# analog.net
KiCad netlist of a schematic drawn in Altium Designer
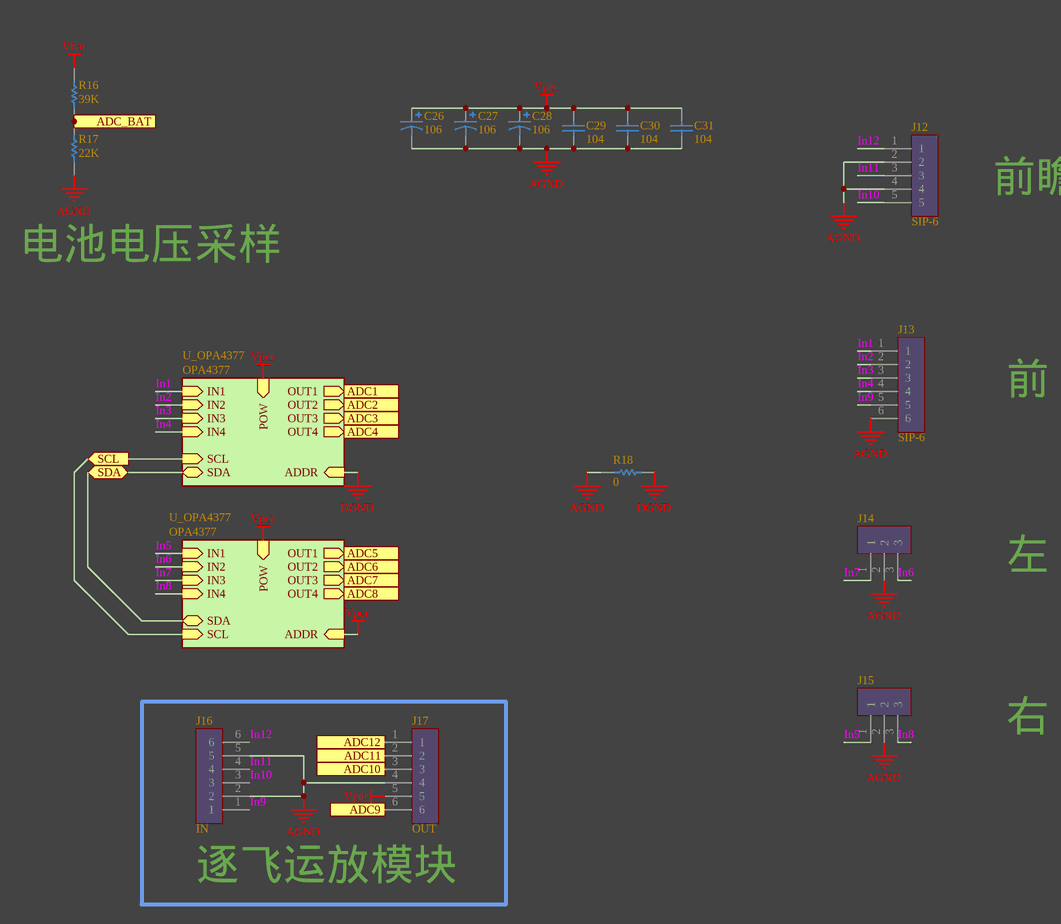
[diagram p0: analog.SchDoc]

(export (version "E")
  (design (tool "Eeschema 10.0.6"))
  (components
    (comp (ref "C26")
      (value "106")
      (footprint "3216-ce")
      (description "Polarized Capacitor (Axial)")
      (fields (field (name "PUBLISHER") "Altium Limited"))
      (libsource (lib "iMag") (part "电解电容"))
    )
    (comp (ref "C27")
      (value "106")
      (footprint "3216-ce")
      (description "Polarized Capacitor (Axial)")
      (fields (field (name "PUBLISHER") "Altium Limited"))
      (libsource (lib "iMag") (part "电解电容"))
    )
    (comp (ref "C28")
      (value "106")
      (footprint "3216-ce")
      (description "Polarized Capacitor (Axial)")
      (fields (field (name "PUBLISHER") "Altium Limited"))
      (libsource (lib "iMag") (part "电解电容"))
    )
    (comp (ref "C29")
      (value "104")
      (footprint "C0402")
      (description "Capacitor")
      (fields (field (name "PUBLISHER") "Altium Limited"))
      (libsource (lib "iMag") (part "电容"))
    )
    (comp (ref "C30")
      (value "104")
      (footprint "C0402")
      (description "Capacitor")
      (fields (field (name "PUBLISHER") "Altium Limited"))
      (libsource (lib "iMag") (part "电容"))
    )
    (comp (ref "C31")
      (value "104")
      (footprint "C0402")
      (description "Capacitor")
      (fields (field (name "PUBLISHER") "Altium Limited"))
      (libsource (lib "iMag") (part "电容"))
    )
    (comp (ref "J12") (value "SIP-6") (footprint "2.54排针1X5") (libsource (lib "iMag") (part "SIP-5")))
    (comp (ref "J13") (value "SIP-6") (footprint "2.54简易牛角座6P") (libsource (lib "iMag") (part "SIP-6")))
    (comp (ref "J14") (value "SIP-3") (footprint "XH2.54-3SMD") (libsource (lib "iMag") (part "SIP-3")))
    (comp (ref "J15") (value "SIP-3") (footprint "XH2.54-3SMD") (libsource (lib "iMag") (part "SIP-3")))
    (comp (ref "J16") (value "IN") (footprint "2.54排针1X6") (libsource (lib "") (part "SIP-6_1")))
    (comp (ref "J17") (value "OUT") (footprint "2.54排针1X6") (libsource (lib "iMag") (part "SIP-6")))
    (comp (ref "R16")
      (value "39K")
      (footprint "R0402")
      (description "Resistor")
      (fields (field (name "PUBLISHER") "Altium Limited"))
      (libsource (lib "iMag") (part "电阻"))
    )
    (comp (ref "R17")
      (value "22K")
      (footprint "R0402")
      (description "Resistor")
      (fields (field (name "PUBLISHER") "Altium Limited"))
      (libsource (lib "iMag") (part "电阻"))
    )
    (comp (ref "R18")
      (value "0")
      (footprint "R0603")
      (description "Resistor")
      (fields (field (name "PUBLISHER") "Altium Limited"))
      (libsource (lib "iMag") (part "电阻"))
    )
  )
  (nets
    (net (code "9") (name "/ADC9") (class "Default")
      (node (ref "J17") (pin "6") (pinfunction "6_6") (pintype "passive"))
    )
    (net (code "10") (name "/ADC10") (class "Default")
      (node (ref "J17") (pin "3") (pinfunction "3_3") (pintype "passive"))
    )
    (net (code "11") (name "/ADC11") (class "Default")
      (node (ref "J17") (pin "2") (pinfunction "2_2") (pintype "passive"))
    )
    (net (code "12") (name "/ADC12") (class "Default")
      (node (ref "J17") (pin "1") (pinfunction "1_1") (pintype "passive"))
    )
    (net (code "13") (name "/ADC_BAT") (class "Default")
      (node (ref "R16") (pin "1") (pinfunction "1_1") (pintype "passive"))
      (node (ref "R17") (pin "2") (pinfunction "2_2") (pintype "passive"))
    )
    (net (code "14") (name "/In1") (class "Default")
      (node (ref "J13") (pin "1") (pinfunction "1_1") (pintype "passive"))
    )
    (net (code "15") (name "/In2") (class "Default")
      (node (ref "J13") (pin "2") (pinfunction "2_2") (pintype "passive"))
    )
    (net (code "16") (name "/In3") (class "Default")
      (node (ref "J13") (pin "3") (pinfunction "3_3") (pintype "passive"))
    )
    (net (code "17") (name "/In4") (class "Default")
      (node (ref "J13") (pin "4") (pinfunction "4_4") (pintype "passive"))
    )
    (net (code "18") (name "/In5") (class "Default")
      (node (ref "J15") (pin "1") (pinfunction "1_1") (pintype "passive"))
    )
    (net (code "19") (name "/In6") (class "Default")
      (node (ref "J14") (pin "3") (pinfunction "3_3") (pintype "passive"))
    )
    (net (code "20") (name "/In7") (class "Default")
      (node (ref "J14") (pin "1") (pinfunction "1_1") (pintype "passive"))
    )
    (net (code "21") (name "/In8") (class "Default")
      (node (ref "J15") (pin "3") (pinfunction "3_3") (pintype "passive"))
    )
    (net (code "22") (name "/In9") (class "Default")
      (node (ref "J13") (pin "5") (pinfunction "5_5") (pintype "passive"))
      (node (ref "J16") (pin "1") (pinfunction "1_1") (pintype "passive"))
    )
    (net (code "23") (name "/In10") (class "Default")
      (node (ref "J12") (pin "5") (pinfunction "5_5") (pintype "passive"))
      (node (ref "J16") (pin "3") (pinfunction "3_3") (pintype "passive"))
    )
    (net (code "24") (name "/In11") (class "Default")
      (node (ref "J12") (pin "3") (pinfunction "3_3") (pintype "passive"))
      (node (ref "J16") (pin "4") (pinfunction "4_4") (pintype "passive"))
    )
    (net (code "25") (name "/In12") (class "Default")
      (node (ref "J12") (pin "1") (pinfunction "1_1") (pintype "passive"))
      (node (ref "J16") (pin "6") (pinfunction "6_6") (pintype "passive"))
    )
    (net (code "28") (name "AGND") (class "Default")
      (node (ref "C26") (pin "2") (pinfunction "2_2") (pintype "passive"))
      (node (ref "C27") (pin "2") (pinfunction "2_2") (pintype "passive"))
      (node (ref "C28") (pin "2") (pinfunction "2_2") (pintype "passive"))
      (node (ref "C29") (pin "1") (pinfunction "1_1") (pintype "passive"))
      (node (ref "C30") (pin "1") (pinfunction "1_1") (pintype "passive"))
      (node (ref "C31") (pin "1") (pinfunction "1_1") (pintype "passive"))
      (node (ref "J12") (pin "2") (pinfunction "2_2") (pintype "passive"))
      (node (ref "J12") (pin "4") (pinfunction "4_4") (pintype "passive"))
      (node (ref "J13") (pin "6") (pinfunction "6_6") (pintype "passive"))
      (node (ref "J14") (pin "2") (pinfunction "2_2") (pintype "passive"))
      (node (ref "J15") (pin "2") (pinfunction "2_2") (pintype "passive"))
      (node (ref "J16") (pin "2") (pinfunction "2_2") (pintype "passive"))
      (node (ref "J16") (pin "5") (pinfunction "5_5") (pintype "passive"))
      (node (ref "J17") (pin "4") (pinfunction "4_4") (pintype "passive"))
      (node (ref "R17") (pin "1") (pinfunction "1_1") (pintype "passive"))
      (node (ref "R18") (pin "2") (pinfunction "2_2") (pintype "passive"))
    )
    (net (code "29") (name "DGND") (class "Default")
      (node (ref "R18") (pin "1") (pinfunction "1_1") (pintype "passive"))
    )
    (net (code "30") (name "Vbat") (class "Default")
      (node (ref "R16") (pin "2") (pinfunction "2_2") (pintype "passive"))
    )
    (net (code "31") (name "Vper") (class "Default")
      (node (ref "C26") (pin "1") (pinfunction "1_1") (pintype "passive"))
      (node (ref "C27") (pin "1") (pinfunction "1_1") (pintype "passive"))
      (node (ref "C28") (pin "1") (pinfunction "1_1") (pintype "passive"))
      (node (ref "C29") (pin "2") (pinfunction "2_2") (pintype "passive"))
      (node (ref "C30") (pin "2") (pinfunction "2_2") (pintype "passive"))
      (node (ref "C31") (pin "2") (pinfunction "2_2") (pintype "passive"))
      (node (ref "J17") (pin "5") (pinfunction "5_5") (pintype "passive"))
    )
  )
)
